# ST_LINK.net
KiCad netlist of a schematic drawn in Altium Designer
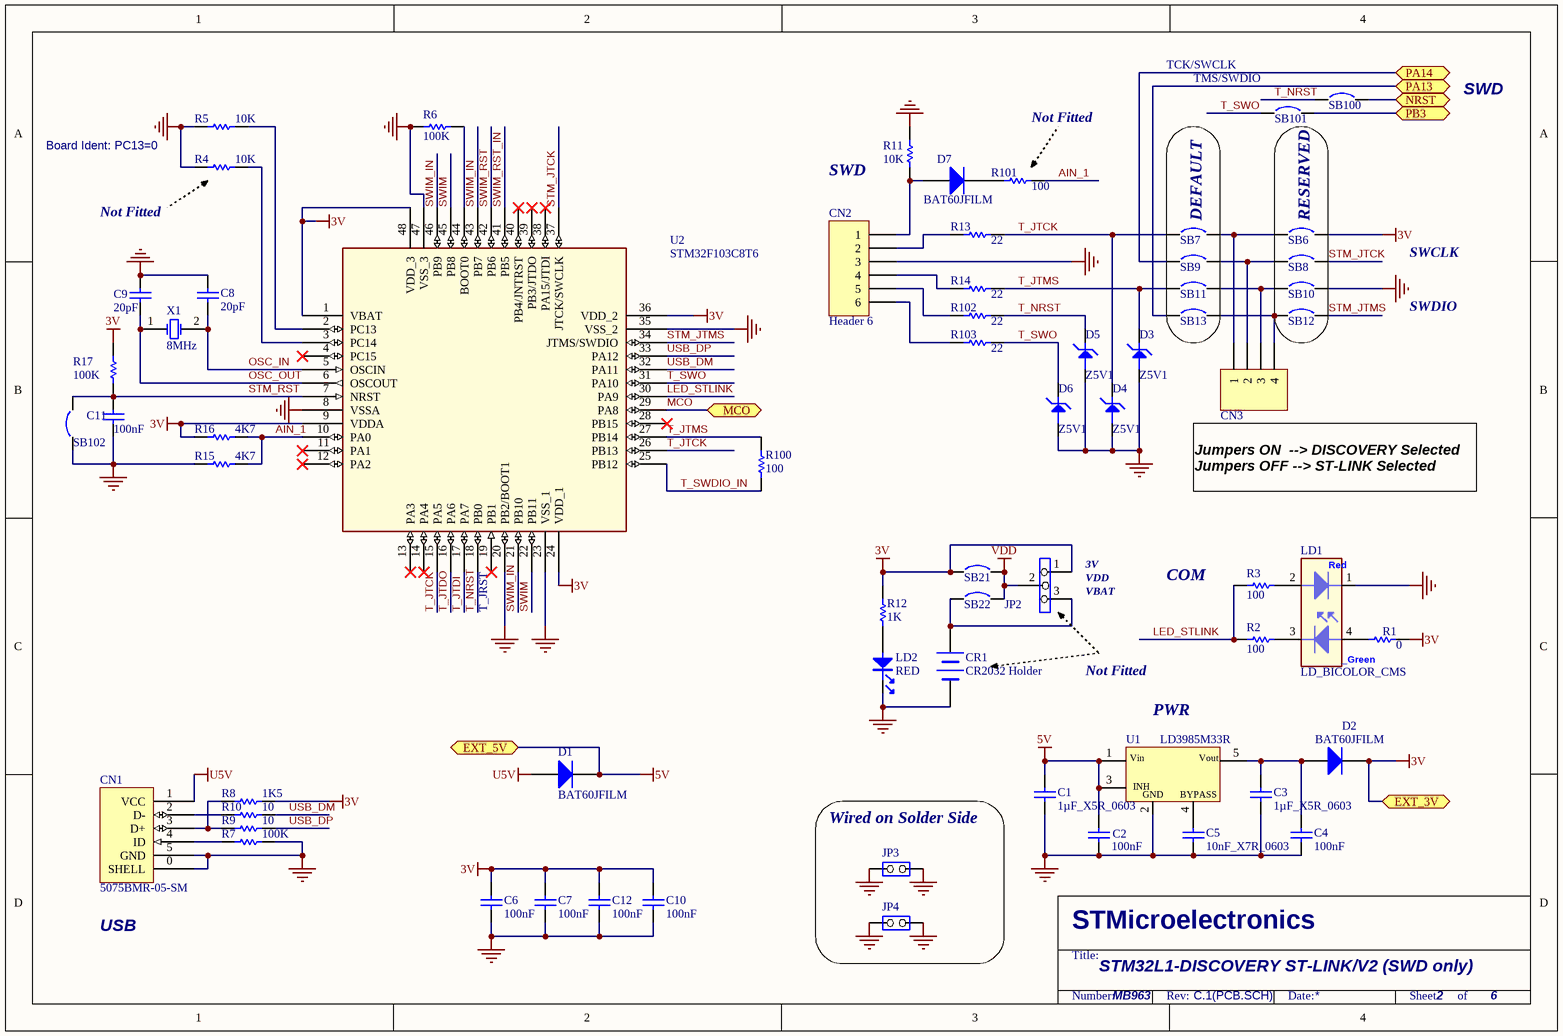
[diagram p0: ST_LINK.SCHDOC]

(export (version "E")
  (design (tool "Eeschema 10.0.6"))
  (components
    (comp (ref "C1")
      (value "1µF_X5R_0603")
      (footprint "0603C")
      (description "0603  X5R 1µF")
      (fields (field (name "TOLERANCE") "10%"))
      (libsource (lib "MB963_1") (part "CAP SMD 0603  X5R 1µF 25V 10%"))
    )
    (comp (ref "C2")
      (value "100nF")
      (footprint "0603C")
      (description "Capacitor")
      (fields (field (name "PUBLISHER") "Altium Limited"))
      (libsource (lib "MB915_1") (part "Cap"))
    )
    (comp (ref "C3")
      (value "1µF_X5R_0603")
      (footprint "0603C")
      (description "0603  X5R 1µF")
      (fields (field (name "TOLERANCE") "10%"))
      (libsource (lib "MB963_1") (part "CAP SMD 0603  X5R 1µF 25V 10%"))
    )
    (comp (ref "C4")
      (value "100nF")
      (footprint "0603C")
      (description "Capacitor")
      (fields (field (name "PUBLISHER") "Altium Limited"))
      (libsource (lib "MB915_1") (part "Cap"))
    )
    (comp (ref "C5")
      (value "10nF_X7R_0603")
      (footprint "0603C")
      (description "0603  X7R 10NF")
      (fields (field (name "TOLERANCE") "10%"))
      (libsource (lib "MB963_1") (part "CAP SMD 0603  X7R 10000PF 50V 10%"))
    )
    (comp (ref "C6")
      (value "100nF")
      (footprint "0402C")
      (description "Capacitor")
      (fields (field (name "PUBLISHER") "Altium Limited"))
      (libsource (lib "MB915_1") (part "Cap"))
    )
    (comp (ref "C7")
      (value "100nF")
      (footprint "0402C")
      (description "Capacitor")
      (fields (field (name "PUBLISHER") "Altium Limited"))
      (libsource (lib "MB915_1") (part "Cap"))
    )
    (comp (ref "C8")
      (value "20pF")
      (footprint "0402C")
      (description "Capacitor")
      (fields (field (name "PUBLISHER") "Altium Limited"))
      (libsource (lib "MB915_1") (part "Cap"))
    )
    (comp (ref "C9")
      (value "20pF")
      (footprint "0402C")
      (description "Capacitor")
      (fields (field (name "PUBLISHER") "Altium Limited"))
      (libsource (lib "MB915_1") (part "Cap"))
    )
    (comp (ref "C10")
      (value "100nF")
      (footprint "0402C")
      (description "Capacitor")
      (fields (field (name "PUBLISHER") "Altium Limited"))
      (libsource (lib "MB915_1") (part "Cap"))
    )
    (comp (ref "C11")
      (value "100nF")
      (footprint "0402C")
      (description "Capacitor")
      (fields (field (name "PUBLISHER") "Altium Limited"))
      (libsource (lib "MB915_1") (part "Cap"))
    )
    (comp (ref "C12")
      (value "100nF")
      (footprint "0402C")
      (description "Capacitor")
      (fields (field (name "PUBLISHER") "Altium Limited"))
      (libsource (lib "MB915_1") (part "Cap"))
    )
    (comp (ref "CN1")
      (value "5075BMR-05-SM")
      (footprint "USB-MINI-B-SMD")
      (libsource (lib "MB963") (part "USB-MINI-typeB connector"))
    )
    (comp (ref "CN2")
      (value "Header 6")
      (footprint "HDR1X6")
      (description "Header, 6-Pin")
      (fields (field (name "PUBLISHER") "Altium Limited"))
      (libsource (lib "Miscellaneous Connectors") (part "Header 6"))
    )
    (comp (ref "CN3")
      (value "Header 4")
      (footprint "Header 4")
      (description "Header, 4-Pin")
      (fields (field (name "PUBLISHER") "Altium Limited"))
      (libsource (lib "MB963_1") (part "Header 4"))
    )
    (comp (ref "CR1")
      (value "CR2032 Holder")
      (footprint "SOCKET BATTERY CR2032 (TRAV)")
      (description "CR2032 socket and battery, KB7410AP2L")
      (libsource (lib "MB963_1") (part "BATTERY"))
    )
    (comp (ref "D1")
      (value "BAT60JFILM")
      (footprint "SOD323/A")
      (description "Default Diode")
      (fields (field (name "PUBLISHER") "Altium Limited"))
      (libsource (lib "MB915_1") (part "Diode"))
    )
    (comp (ref "D2")
      (value "BAT60JFILM")
      (footprint "SOD323/A")
      (description "Default Diode")
      (fields (field (name "PUBLISHER") "Altium Limited"))
      (libsource (lib "MB915_1") (part "Diode"))
    )
    (comp (ref "D3")
      (value "Z5V1")
      (footprint "SOT-23")
      (description "BZX84-C5V6")
      (libsource (lib "MB963_1") (part "Z5V6"))
    )
    (comp (ref "D4")
      (value "Z5V1")
      (footprint "SOT-23")
      (description "BZX84-C5V6")
      (libsource (lib "MB963_1") (part "Z5V6"))
    )
    (comp (ref "D5")
      (value "Z5V1")
      (footprint "SOT-23")
      (description "BZX84-C5V6")
      (libsource (lib "MB963_1") (part "Z5V6"))
    )
    (comp (ref "D6")
      (value "Z5V1")
      (footprint "SOT-23")
      (description "BZX84-C5V6")
      (libsource (lib "MB963_1") (part "Z5V6"))
    )
    (comp (ref "D7")
      (value "BAT60JFILM")
      (footprint "SOD323/A")
      (description "Default Diode")
      (fields (field (name "PUBLISHER") "Altium Limited"))
      (libsource (lib "MB915_1") (part "Diode"))
    )
    (comp (ref "JP2") (value "~") (footprint "SIP3") (libsource (lib "STR910_SCHLIB") (part "Jumper3")))
    (comp (ref "JP3") (value "~") (footprint "SIP2/2.54") (libsource (lib "*") (part "JP2")))
    (comp (ref "JP4") (value "~") (footprint "SIP2/2.54") (libsource (lib "*") (part "JP2")))
    (comp (ref "LD1")
      (value "LD_BICOLOR_CMS")
      (footprint "HSMF-A201")
      (description "Bicolor Led")
      (libsource (lib "MB963") (part "LD_BICOLOR_CMS"))
    )
    (comp (ref "LD2") (value "RED") (footprint "0603D") (libsource (lib "MB963_1") (part "PHOTO")))
    (comp (ref "R1")
      (value "0")
      (footprint "0402R")
      (description "Resistor")
      (fields (field (name "PUBLISHER") "Altium Limited"))
      (libsource (lib "MB915_1") (part "res1"))
    )
    (comp (ref "R2")
      (value "100")
      (footprint "0402R")
      (description "Resistor")
      (fields (field (name "PUBLISHER") "Altium Limited"))
      (libsource (lib "MB915_1") (part "res1"))
    )
    (comp (ref "R3")
      (value "100")
      (footprint "0402R")
      (description "Resistor")
      (fields (field (name "PUBLISHER") "Altium Limited"))
      (libsource (lib "MB915_1") (part "res1"))
    )
    (comp (ref "R4")
      (value "10K")
      (footprint "0402R")
      (description "Resistor")
      (fields (field (name "PUBLISHER") "Altium Limited"))
      (libsource (lib "MB915_1") (part "res1"))
    )
    (comp (ref "R5")
      (value "10K")
      (footprint "0402R")
      (description "Resistor")
      (fields (field (name "PUBLISHER") "Altium Limited"))
      (libsource (lib "MB915_1") (part "res1"))
    )
    (comp (ref "R6")
      (value "100K")
      (footprint "0402R")
      (description "Resistor")
      (fields (field (name "PUBLISHER") "Altium Limited"))
      (libsource (lib "MB915_1") (part "res1"))
    )
    (comp (ref "R7")
      (value "100K")
      (footprint "0402R")
      (description "Resistor")
      (fields (field (name "PUBLISHER") "Altium Limited"))
      (libsource (lib "MB915_1") (part "res1"))
    )
    (comp (ref "R8")
      (value "1K5")
      (footprint "0402R")
      (description "Resistor")
      (fields (field (name "PUBLISHER") "Altium Limited"))
      (libsource (lib "MB915_1") (part "res1"))
    )
    (comp (ref "R9")
      (value "10")
      (footprint "0603R")
      (description "Resistor")
      (fields (field (name "PUBLISHER") "Altium Limited"))
      (libsource (lib "MB915_1") (part "res1"))
    )
    (comp (ref "R10")
      (value "10")
      (footprint "0603R")
      (description "Resistor")
      (fields (field (name "PUBLISHER") "Altium Limited"))
      (libsource (lib "MB915_1") (part "res1"))
    )
    (comp (ref "R11")
      (value "10K")
      (footprint "0402R")
      (description "Resistor")
      (fields (field (name "PUBLISHER") "Altium Limited"))
      (libsource (lib "MB915_1") (part "res1"))
    )
    (comp (ref "R12")
      (value "1K")
      (footprint "0402R")
      (description "Resistor")
      (fields (field (name "PUBLISHER") "Altium Limited"))
      (libsource (lib "MB915_1") (part "res1"))
    )
    (comp (ref "R13")
      (value "22")
      (footprint "0402R")
      (description "Resistor")
      (fields (field (name "PUBLISHER") "Altium Limited"))
      (libsource (lib "MB915_1") (part "res1"))
    )
    (comp (ref "R14")
      (value "22")
      (footprint "0402R")
      (description "Resistor")
      (fields (field (name "PUBLISHER") "Altium Limited"))
      (libsource (lib "MB915_1") (part "res1"))
    )
    (comp (ref "R15")
      (value "4K7")
      (footprint "0402R")
      (description "Resistor")
      (fields (field (name "PUBLISHER") "Altium Limited"))
      (libsource (lib "MB915_1") (part "res1"))
    )
    (comp (ref "R16")
      (value "4K7")
      (footprint "0402R")
      (description "Resistor")
      (fields (field (name "PUBLISHER") "Altium Limited"))
      (libsource (lib "MB915_1") (part "res1"))
    )
    (comp (ref "R17")
      (value "100K")
      (footprint "0402R")
      (description "Resistor")
      (fields (field (name "PUBLISHER") "Altium Limited"))
      (libsource (lib "MB915_1") (part "res1"))
    )
    (comp (ref "R100")
      (value "100")
      (footprint "0402R")
      (description "Resistor")
      (fields (field (name "PUBLISHER") "Altium Limited"))
      (libsource (lib "MB915_1") (part "res1"))
    )
    (comp (ref "R101")
      (value "100")
      (footprint "0402R")
      (description "Resistor")
      (fields (field (name "PUBLISHER") "Altium Limited"))
      (libsource (lib "MB915_1") (part "res1"))
    )
    (comp (ref "R102")
      (value "22")
      (footprint "0402R")
      (description "Resistor")
      (fields (field (name "PUBLISHER") "Altium Limited"))
      (libsource (lib "MB915_1") (part "res1"))
    )
    (comp (ref "R103")
      (value "22")
      (footprint "0402R")
      (description "Resistor")
      (fields (field (name "PUBLISHER") "Altium Limited"))
      (libsource (lib "MB915_1") (part "res1"))
    )
    (comp (ref "SB6")
      (value "Circuit Breaker")
      (footprint "JP2_SMD")
      (fields (field (name "PUBLISHER") "Altium Limited"))
      (libsource (lib "MB915") (part "Circuit Breaker"))
    )
    (comp (ref "SB7")
      (value "Circuit Breaker")
      (footprint "JP2_SMD")
      (fields (field (name "PUBLISHER") "Altium Limited"))
      (libsource (lib "MB915") (part "Circuit Breaker"))
    )
    (comp (ref "SB8")
      (value "Circuit Breaker")
      (footprint "JP2_SMD")
      (fields (field (name "PUBLISHER") "Altium Limited"))
      (libsource (lib "MB915") (part "Circuit Breaker"))
    )
    (comp (ref "SB9")
      (value "Circuit Breaker")
      (footprint "JP2_SMD")
      (fields (field (name "PUBLISHER") "Altium Limited"))
      (libsource (lib "MB915") (part "Circuit Breaker"))
    )
    (comp (ref "SB10")
      (value "Circuit Breaker")
      (footprint "JP2_SMD")
      (fields (field (name "PUBLISHER") "Altium Limited"))
      (libsource (lib "MB915") (part "Circuit Breaker"))
    )
    (comp (ref "SB11")
      (value "Circuit Breaker")
      (footprint "JP2_SMD")
      (fields (field (name "PUBLISHER") "Altium Limited"))
      (libsource (lib "MB915") (part "Circuit Breaker"))
    )
    (comp (ref "SB12")
      (value "Circuit Breaker")
      (footprint "JP2_SMD")
      (fields (field (name "PUBLISHER") "Altium Limited"))
      (libsource (lib "MB915") (part "Circuit Breaker"))
    )
    (comp (ref "SB13")
      (value "Circuit Breaker")
      (footprint "JP2_SMD")
      (fields (field (name "PUBLISHER") "Altium Limited"))
      (libsource (lib "MB915") (part "Circuit Breaker"))
    )
    (comp (ref "SB21")
      (value "Circuit Breaker")
      (footprint "JP2_SMD")
      (fields (field (name "PUBLISHER") "Altium Limited"))
      (libsource (lib "MB915") (part "Circuit Breaker"))
    )
    (comp (ref "SB22")
      (value "Circuit Breaker")
      (footprint "JP2_SMD")
      (fields (field (name "PUBLISHER") "Altium Limited"))
      (libsource (lib "MB915") (part "Circuit Breaker"))
    )
    (comp (ref "SB100")
      (value "Circuit Breaker")
      (footprint "JP2_SMD")
      (fields (field (name "PUBLISHER") "Altium Limited"))
      (libsource (lib "MB915") (part "Circuit Breaker"))
    )
    (comp (ref "SB101")
      (value "Circuit Breaker")
      (footprint "JP2_SMD")
      (fields (field (name "PUBLISHER") "Altium Limited"))
      (libsource (lib "MB915") (part "Circuit Breaker"))
    )
    (comp (ref "SB102")
      (value "Circuit Breaker")
      (footprint "JP2_SMD")
      (fields (field (name "PUBLISHER") "Altium Limited"))
      (libsource (lib "MB915") (part "Circuit Breaker"))
    )
    (comp (ref "U1") (value "LD3985M33R") (footprint "SOT-23-5L") (libsource (lib "Common") (part "LD3985")))
    (comp (ref "U2")
      (value "STM32F103C8T6")
      (footprint "QFP48 7X7")
      (libsource (lib "MB963") (part "STM32F103C8T6"))
    )
    (comp (ref "X1")
      (value "8MHz")
      (footprint "XTAL1")
      (description "Crystal Oscillator")
      (fields (field (name "PUBLISHER") "Altium Limited"))
      (libsource (lib "MB963_1") (part "XTAL"))
    )
  )
  (nets
    (net (code "1") (name "/AIN_1") (class "Default")
      (node (ref "R101") (pin "2") (pinfunction "2_2") (pintype "passive"))
      (node (ref "R15") (pin "2") (pinfunction "2_2") (pintype "passive"))
      (node (ref "R16") (pin "2") (pinfunction "2_2") (pintype "passive"))
      (node (ref "U2") (pin "10") (pinfunction "PA0_10") (pintype "bidirectional"))
    )
    (net (code "2") (name "/LED_STLINK") (class "Default")
      (node (ref "R2") (pin "1") (pinfunction "1_1") (pintype "passive"))
      (node (ref "R3") (pin "1") (pinfunction "1_1") (pintype "passive"))
      (node (ref "U2") (pin "30") (pinfunction "PA9_30") (pintype "bidirectional"))
    )
    (net (code "3") (name "/MCO") (class "Default")
      (node (ref "U2") (pin "29") (pinfunction "PA8_29") (pintype "bidirectional"))
    )
    (net (code "4") (name "/NRST") (class "Default")
      (node (ref "SB100") (pin "2") (pinfunction "2_2") (pintype "passive"))
    )
    (net (code "5") (name "/OSC_IN") (class "Default")
      (node (ref "C8") (pin "2") (pinfunction "2_2") (pintype "passive"))
      (node (ref "U2") (pin "5") (pinfunction "OSCIN_5") (pintype "input"))
      (node (ref "X1") (pin "2") (pinfunction "OSC2_2") (pintype "passive"))
    )
    (net (code "6") (name "/OSC_OUT") (class "Default")
      (node (ref "C9") (pin "2") (pinfunction "2_2") (pintype "passive"))
      (node (ref "U2") (pin "6") (pinfunction "OSCOUT_6") (pintype "output"))
      (node (ref "X1") (pin "1") (pinfunction "OSC1_1") (pintype "passive"))
    )
    (net (code "7") (name "/PA13") (class "Default")
      (node (ref "SB13") (pin "1") (pinfunction "1_1") (pintype "passive"))
    )
    (net (code "8") (name "/PA14") (class "Default")
      (node (ref "SB9") (pin "1") (pinfunction "1_1") (pintype "passive"))
    )
    (net (code "9") (name "/PB3") (class "Default")
      (node (ref "SB101") (pin "2") (pinfunction "2_2") (pintype "passive"))
    )
    (net (code "10") (name "/STM_JTCK") (class "Default")
      (node (ref "SB8") (pin "2") (pinfunction "2_2") (pintype "passive"))
      (node (ref "U2") (pin "37") (pinfunction "JTCK/SWCLK_37") (pintype "bidirectional"))
    )
    (net (code "11") (name "/STM_JTMS") (class "Default")
      (node (ref "SB12") (pin "2") (pinfunction "2_2") (pintype "passive"))
      (node (ref "U2") (pin "34") (pinfunction "JTMS/SWDIO_34") (pintype "bidirectional"))
    )
    (net (code "12") (name "/STM_RST") (class "Default")
      (node (ref "C11") (pin "2") (pinfunction "2_2") (pintype "passive"))
      (node (ref "R17") (pin "1") (pinfunction "1_1") (pintype "passive"))
      (node (ref "SB102") (pin "2") (pinfunction "2_2") (pintype "passive"))
      (node (ref "U2") (pin "7") (pinfunction "NRST_7") (pintype "input"))
    )
    (net (code "13") (name "/SWIM") (class "Default")
      (node (ref "U2") (pin "22") (pinfunction "PB11_22") (pintype "bidirectional"))
      (node (ref "U2") (pin "45") (pinfunction "PB8_45") (pintype "bidirectional"))
    )
    (net (code "14") (name "/SWIM_IN") (class "Default")
      (node (ref "U2") (pin "21") (pinfunction "PB10_21") (pintype "bidirectional"))
      (node (ref "U2") (pin "43") (pinfunction "PB7_43") (pintype "bidirectional"))
      (node (ref "U2") (pin "46") (pinfunction "PB9_46") (pintype "bidirectional"))
    )
    (net (code "15") (name "/SWIM_RST") (class "Default")
      (node (ref "U2") (pin "42") (pinfunction "PB6_42") (pintype "bidirectional"))
    )
    (net (code "16") (name "/SWIM_RST_IN") (class "Default")
      (node (ref "U2") (pin "41") (pinfunction "PB5_41") (pintype "bidirectional"))
    )
    (net (code "17") (name "/T_JTCK") (class "Default")
      (node (ref "D4") (pin "3") (pintype "passive"))
      (node (ref "R13") (pin "2") (pinfunction "2_2") (pintype "passive"))
      (node (ref "SB7") (pin "1") (pinfunction "1_1") (pintype "passive"))
      (node (ref "U2") (pin "15") (pinfunction "PA5_15") (pintype "bidirectional"))
      (node (ref "U2") (pin "26") (pinfunction "PB13_26") (pintype "bidirectional"))
    )
    (net (code "18") (name "/T_JTDI") (class "Default")
      (node (ref "U2") (pin "17") (pinfunction "PA7_17") (pintype "bidirectional"))
    )
    (net (code "19") (name "/T_JTDO") (class "Default")
      (node (ref "U2") (pin "16") (pinfunction "PA6_16") (pintype "bidirectional"))
    )
    (net (code "20") (name "/T_JTMS") (class "Default")
      (node (ref "D3") (pin "3") (pintype "passive"))
      (node (ref "R100") (pin "2") (pinfunction "2_2") (pintype "passive"))
      (node (ref "R14") (pin "2") (pinfunction "2_2") (pintype "passive"))
      (node (ref "SB11") (pin "1") (pinfunction "1_1") (pintype "passive"))
      (node (ref "U2") (pin "27") (pinfunction "PB14_27") (pintype "bidirectional"))
    )
    (net (code "21") (name "/T_NRST") (class "Default")
      (node (ref "D5") (pin "3") (pintype "passive"))
      (node (ref "R102") (pin "2") (pinfunction "2_2") (pintype "passive"))
      (node (ref "SB100") (pin "1") (pinfunction "1_1") (pintype "passive"))
      (node (ref "U2") (pin "18") (pinfunction "PB0_18") (pintype "bidirectional"))
    )
    (net (code "22") (name "/T_SWDIO_IN") (class "Default")
      (node (ref "R100") (pin "1") (pinfunction "1_1") (pintype "passive"))
      (node (ref "U2") (pin "25") (pinfunction "PB12_25") (pintype "bidirectional"))
    )
    (net (code "23") (name "/T_SWO") (class "Default")
      (node (ref "D6") (pin "3") (pintype "passive"))
      (node (ref "R103") (pin "2") (pinfunction "2_2") (pintype "passive"))
      (node (ref "SB101") (pin "1") (pinfunction "1_1") (pintype "passive"))
      (node (ref "U2") (pin "31") (pinfunction "PA10_31") (pintype "bidirectional"))
    )
    (net (code "24") (name "/USB_DM") (class "Default")
      (node (ref "R10") (pin "2") (pinfunction "2_2") (pintype "passive"))
      (node (ref "U2") (pin "32") (pinfunction "PA11_32") (pintype "bidirectional"))
    )
    (net (code "25") (name "/USB_DP") (class "Default")
      (node (ref "R9") (pin "2") (pinfunction "2_2") (pintype "passive"))
      (node (ref "U2") (pin "33") (pinfunction "PA12_33") (pintype "bidirectional"))
    )
    (net (code "26") (name "3V") (class "Default")
      (node (ref "C10") (pin "2") (pinfunction "2_2") (pintype "passive"))
      (node (ref "C12") (pin "1") (pinfunction "1_1") (pintype "passive"))
      (node (ref "C6") (pin "2") (pinfunction "2_2") (pintype "passive"))
      (node (ref "C7") (pin "2") (pinfunction "2_2") (pintype "passive"))
      (node (ref "D2") (pin "2") (pinfunction "K_2") (pintype "passive"))
      (node (ref "JP2") (pin "1") (pintype "passive"))
      (node (ref "R1") (pin "2") (pinfunction "2_2") (pintype "passive"))
      (node (ref "R12") (pin "2") (pinfunction "2_2") (pintype "passive"))
      (node (ref "R16") (pin "1") (pinfunction "1_1") (pintype "passive"))
      (node (ref "R17") (pin "2") (pinfunction "2_2") (pintype "passive"))
      (node (ref "R8") (pin "2") (pinfunction "2_2") (pintype "passive"))
      (node (ref "SB21") (pin "1") (pinfunction "1_1") (pintype "passive"))
      (node (ref "SB6") (pin "2") (pinfunction "2_2") (pintype "passive"))
      (node (ref "U2") (pin "1") (pinfunction "VBAT_1") (pintype "power_in"))
      (node (ref "U2") (pin "24") (pinfunction "VDD_1_24") (pintype "power_in"))
      (node (ref "U2") (pin "36") (pinfunction "VDD_2_36") (pintype "power_in"))
      (node (ref "U2") (pin "48") (pinfunction "VDD_3_48") (pintype "power_in"))
      (node (ref "U2") (pin "9") (pinfunction "VDDA_9") (pintype "power_in"))
    )
    (net (code "27") (name "5V") (class "Default")
      (node (ref "C1") (pin "2") (pinfunction "2_2") (pintype "passive"))
      (node (ref "C2") (pin "2") (pinfunction "2_2") (pintype "passive"))
      (node (ref "D1") (pin "2") (pinfunction "K_2") (pintype "passive"))
      (node (ref "U1") (pin "1") (pinfunction "Vin_1") (pintype "passive"))
      (node (ref "U1") (pin "3") (pinfunction "CE_3") (pintype "passive"))
    )
    (net (code "28") (name "GND") (class "Default")
      (node (ref "C1") (pin "1") (pinfunction "1_1") (pintype "passive"))
      (node (ref "C10") (pin "1") (pinfunction "1_1") (pintype "passive"))
      (node (ref "C11") (pin "1") (pinfunction "1_1") (pintype "passive"))
      (node (ref "C12") (pin "2") (pinfunction "2_2") (pintype "passive"))
      (node (ref "C2") (pin "1") (pinfunction "1_1") (pintype "passive"))
      (node (ref "C3") (pin "2") (pinfunction "2_2") (pintype "passive"))
      (node (ref "C4") (pin "1") (pinfunction "1_1") (pintype "passive"))
      (node (ref "C5") (pin "1") (pinfunction "1_1") (pintype "passive"))
      (node (ref "C6") (pin "1") (pinfunction "1_1") (pintype "passive"))
      (node (ref "C7") (pin "1") (pinfunction "1_1") (pintype "passive"))
      (node (ref "C8") (pin "1") (pinfunction "1_1") (pintype "passive"))
      (node (ref "C9") (pin "1") (pinfunction "1_1") (pintype "passive"))
      (node (ref "CN1") (pin "0") (pinfunction "SHELL_0") (pintype "power_in"))
      (node (ref "CN1") (pin "5") (pinfunction "GND_5") (pintype "power_in"))
      (node (ref "CN2") (pin "3") (pinfunction "3_3") (pintype "passive"))
      (node (ref "CR1") (pin "2") (pinfunction "-_2") (pintype "passive"))
      (node (ref "D3") (pin "2") (pintype "passive"))
      (node (ref "D4") (pin "2") (pintype "passive"))
      (node (ref "D5") (pin "2") (pintype "passive"))
      (node (ref "D6") (pin "2") (pintype "passive"))
      (node (ref "JP3") (pin "1") (pinfunction "COMMON_1") (pintype "passive"))
      (node (ref "JP3") (pin "2") (pinfunction "NO_2") (pintype "passive"))
      (node (ref "JP4") (pin "1") (pinfunction "COMMON_1") (pintype "passive"))
      (node (ref "JP4") (pin "2") (pinfunction "NO_2") (pintype "passive"))
      (node (ref "LD1") (pin "1") (pinfunction "1_1") (pintype "passive"))
      (node (ref "LD2") (pin "2") (pintype "passive"))
      (node (ref "R11") (pin "2") (pinfunction "2_2") (pintype "passive"))
      (node (ref "R15") (pin "1") (pinfunction "1_1") (pintype "passive"))
      (node (ref "R4") (pin "1") (pinfunction "1_1") (pintype "passive"))
      (node (ref "R5") (pin "1") (pinfunction "1_1") (pintype "passive"))
      (node (ref "R6") (pin "1") (pinfunction "1_1") (pintype "passive"))
      (node (ref "R7") (pin "2") (pinfunction "2_2") (pintype "passive"))
      (node (ref "SB10") (pin "2") (pinfunction "2_2") (pintype "passive"))
      (node (ref "SB102") (pin "1") (pinfunction "1_1") (pintype "passive"))
      (node (ref "U1") (pin "2") (pinfunction "GND_2") (pintype "passive"))
      (node (ref "U2") (pin "20") (pinfunction "PB2/BOOT1_20") (pintype "bidirectional"))
      (node (ref "U2") (pin "23") (pinfunction "VSS_1_23") (pintype "power_in"))
      (node (ref "U2") (pin "35") (pinfunction "VSS_2_35") (pintype "power_in"))
      (node (ref "U2") (pin "47") (pinfunction "VSS_3_47") (pintype "power_in"))
      (node (ref "U2") (pin "8") (pinfunction "VSSA_8") (pintype "power_in"))
    )
    (net (code "29") (name "Net-(CN1-D+)") (class "Default")
      (node (ref "CN1") (pin "3") (pinfunction "D+_3") (pintype "bidirectional"))
      (node (ref "R8") (pin "1") (pinfunction "1_1") (pintype "passive"))
      (node (ref "R9") (pin "1") (pinfunction "1_1") (pintype "passive"))
    )
    (net (code "30") (name "Net-(CN1-D-)") (class "Default")
      (node (ref "CN1") (pin "2") (pinfunction "D-_2") (pintype "bidirectional"))
      (node (ref "R10") (pin "1") (pinfunction "1_1") (pintype "passive"))
    )
    (net (code "31") (name "Net-(CN1-ID)") (class "Default")
      (node (ref "CN1") (pin "4") (pinfunction "ID_4") (pintype "input"))
      (node (ref "R7") (pin "1") (pinfunction "1_1") (pintype "passive"))
    )
    (net (code "32") (name "Net-(CN2-Pad2)") (class "Default")
      (node (ref "CN2") (pin "2") (pinfunction "2_2") (pintype "passive"))
      (node (ref "R13") (pin "1") (pinfunction "1_1") (pintype "passive"))
    )
    (net (code "33") (name "Net-(CN2-Pad4)") (class "Default")
      (node (ref "CN2") (pin "4") (pinfunction "4_4") (pintype "passive"))
      (node (ref "R14") (pin "1") (pinfunction "1_1") (pintype "passive"))
    )
    (net (code "34") (name "Net-(CN2-Pad5)") (class "Default")
      (node (ref "CN2") (pin "5") (pinfunction "5_5") (pintype "passive"))
      (node (ref "R102") (pin "1") (pinfunction "1_1") (pintype "passive"))
    )
    (net (code "35") (name "Net-(CN2-Pad6)") (class "Default")
      (node (ref "CN2") (pin "6") (pinfunction "6_6") (pintype "passive"))
      (node (ref "R103") (pin "1") (pinfunction "1_1") (pintype "passive"))
    )
    (net (code "36") (name "Net-(CN3-Pad1)") (class "Default")
      (node (ref "CN3") (pin "1") (pinfunction "1_1") (pintype "passive"))
      (node (ref "SB6") (pin "1") (pinfunction "1_1") (pintype "passive"))
      (node (ref "SB7") (pin "2") (pinfunction "2_2") (pintype "passive"))
    )
    (net (code "37") (name "Net-(CN3-Pad2)") (class "Default")
      (node (ref "CN3") (pin "2") (pinfunction "2_2") (pintype "passive"))
      (node (ref "SB8") (pin "1") (pinfunction "1_1") (pintype "passive"))
      (node (ref "SB9") (pin "2") (pinfunction "2_2") (pintype "passive"))
    )
    (net (code "38") (name "Net-(CN3-Pad3)") (class "Default")
      (node (ref "CN3") (pin "3") (pinfunction "3_3") (pintype "passive"))
      (node (ref "SB10") (pin "1") (pinfunction "1_1") (pintype "passive"))
      (node (ref "SB11") (pin "2") (pinfunction "2_2") (pintype "passive"))
    )
    (net (code "39") (name "Net-(CN3-Pad4)") (class "Default")
      (node (ref "CN3") (pin "4") (pinfunction "4_4") (pintype "passive"))
      (node (ref "SB12") (pin "1") (pinfunction "1_1") (pintype "passive"))
      (node (ref "SB13") (pin "2") (pinfunction "2_2") (pintype "passive"))
    )
    (net (code "40") (name "Net-(CR1-+)") (class "Default")
      (node (ref "CR1") (pin "1") (pinfunction "+_1") (pintype "passive"))
      (node (ref "JP2") (pin "3") (pintype "passive"))
      (node (ref "SB22") (pin "1") (pinfunction "1_1") (pintype "passive"))
    )
    (net (code "41") (name "Net-(D2-A)") (class "Default")
      (node (ref "C3") (pin "1") (pinfunction "1_1") (pintype "passive"))
      (node (ref "C4") (pin "2") (pinfunction "2_2") (pintype "passive"))
      (node (ref "D2") (pin "1") (pinfunction "A_1") (pintype "passive"))
      (node (ref "U1") (pin "5") (pinfunction "Vout_5") (pintype "passive"))
    )
    (net (code "42") (name "Net-(D7-A)") (class "Default")
      (node (ref "CN2") (pin "1") (pinfunction "1_1") (pintype "passive"))
      (node (ref "D7") (pin "1") (pinfunction "A_1") (pintype "passive"))
      (node (ref "R11") (pin "1") (pinfunction "1_1") (pintype "passive"))
    )
    (net (code "43") (name "Net-(D7-K)") (class "Default")
      (node (ref "D7") (pin "2") (pinfunction "K_2") (pintype "passive"))
      (node (ref "R101") (pin "1") (pinfunction "1_1") (pintype "passive"))
    )
    (net (code "44") (name "Net-(LD1-Pad2)") (class "Default")
      (node (ref "LD1") (pin "2") (pinfunction "2_2") (pintype "passive"))
      (node (ref "R3") (pin "2") (pinfunction "2_2") (pintype "passive"))
    )
    (net (code "45") (name "Net-(LD1-Pad3)") (class "Default")
      (node (ref "LD1") (pin "3") (pinfunction "3_3") (pintype "passive"))
      (node (ref "R2") (pin "2") (pinfunction "2_2") (pintype "passive"))
    )
    (net (code "46") (name "Net-(LD1-Pad4)") (class "Default")
      (node (ref "LD1") (pin "4") (pinfunction "4_4") (pintype "passive"))
      (node (ref "R1") (pin "1") (pinfunction "1_1") (pintype "passive"))
    )
    (net (code "47") (name "Net-(LD2-Pad1)") (class "Default")
      (node (ref "LD2") (pin "1") (pintype "passive"))
      (node (ref "R12") (pin "1") (pinfunction "1_1") (pintype "passive"))
    )
    (net (code "48") (name "Net-(U1-BYPASS)") (class "Default")
      (node (ref "C5") (pin "2") (pinfunction "2_2") (pintype "passive"))
      (node (ref "U1") (pin "4") (pinfunction "BYPASS_4") (pintype "passive"))
    )
    (net (code "49") (name "Net-(U2-BOOT0)") (class "Default")
      (node (ref "R6") (pin "2") (pinfunction "2_2") (pintype "passive"))
      (node (ref "U2") (pin "44") (pinfunction "BOOT0_44") (pintype "bidirectional"))
    )
    (net (code "50") (name "Net-(U2-PC13)") (class "Default")
      (node (ref "R5") (pin "2") (pinfunction "2_2") (pintype "passive"))
      (node (ref "U2") (pin "2") (pinfunction "PC13_2") (pintype "bidirectional"))
    )
    (net (code "51") (name "Net-(U2-PC14)") (class "Default")
      (node (ref "R4") (pin "2") (pinfunction "2_2") (pintype "passive"))
      (node (ref "U2") (pin "3") (pinfunction "PC14_3") (pintype "bidirectional"))
    )
    (net (code "52") (name "U5V") (class "Default")
      (node (ref "CN1") (pin "1") (pinfunction "VCC_1") (pintype "power_in"))
      (node (ref "D1") (pin "1") (pinfunction "A_1") (pintype "passive"))
    )
    (net (code "53") (name "VDD") (class "Default")
      (node (ref "JP2") (pin "2") (pintype "passive"))
      (node (ref "SB21") (pin "2") (pinfunction "2_2") (pintype "passive"))
      (node (ref "SB22") (pin "2") (pinfunction "2_2") (pintype "passive"))
    )
    (net (code "54") (name "unconnected-(U2-PA1-Pad11)") (class "Default")
      (node (ref "U2") (pin "11") (pinfunction "PA1_11") (pintype "bidirectional+no_connect"))
    )
    (net (code "55") (name "unconnected-(U2-PA2-Pad12)") (class "Default")
      (node (ref "U2") (pin "12") (pinfunction "PA2_12") (pintype "bidirectional+no_connect"))
    )
    (net (code "56") (name "unconnected-(U2-PA3-Pad13)") (class "Default")
      (node (ref "U2") (pin "13") (pinfunction "PA3_13") (pintype "bidirectional+no_connect"))
    )
    (net (code "57") (name "unconnected-(U2-PA4-Pad14)") (class "Default")
      (node (ref "U2") (pin "14") (pinfunction "PA4_14") (pintype "bidirectional+no_connect"))
    )
    (net (code "58") (name "unconnected-(U2-PA15{slash}JTDI-Pad38)") (class "Default")
      (node (ref "U2") (pin "38") (pinfunction "PA15/JTDI_38") (pintype "bidirectional+no_connect"))
    )
    (net (code "59") (name "unconnected-(U2-PB1-Pad19)") (class "Default")
      (node (ref "U2") (pin "19") (pinfunction "PB1_19") (pintype "input+no_connect"))
    )
    (net (code "60") (name "unconnected-(U2-PB3{slash}JTDO-Pad39)") (class "Default")
      (node (ref "U2") (pin "39") (pinfunction "PB3/JTDO_39") (pintype "bidirectional+no_connect"))
    )
    (net (code "61") (name "unconnected-(U2-PB4{slash}JNTRST-Pad40)") (class "Default")
      (node (ref "U2") (pin "40") (pinfunction "PB4/JNTRST_40") (pintype "bidirectional+no_connect"))
    )
    (net (code "62") (name "unconnected-(U2-PB15-Pad28)") (class "Default")
      (node (ref "U2") (pin "28") (pinfunction "PB15_28") (pintype "bidirectional+no_connect"))
    )
    (net (code "63") (name "unconnected-(U2-PC15-Pad4)") (class "Default")
      (node (ref "U2") (pin "4") (pinfunction "PC15_4") (pintype "bidirectional+no_connect"))
    )
  )
)
